# power.net
KiCad netlist of a schematic drawn in Altium Designer
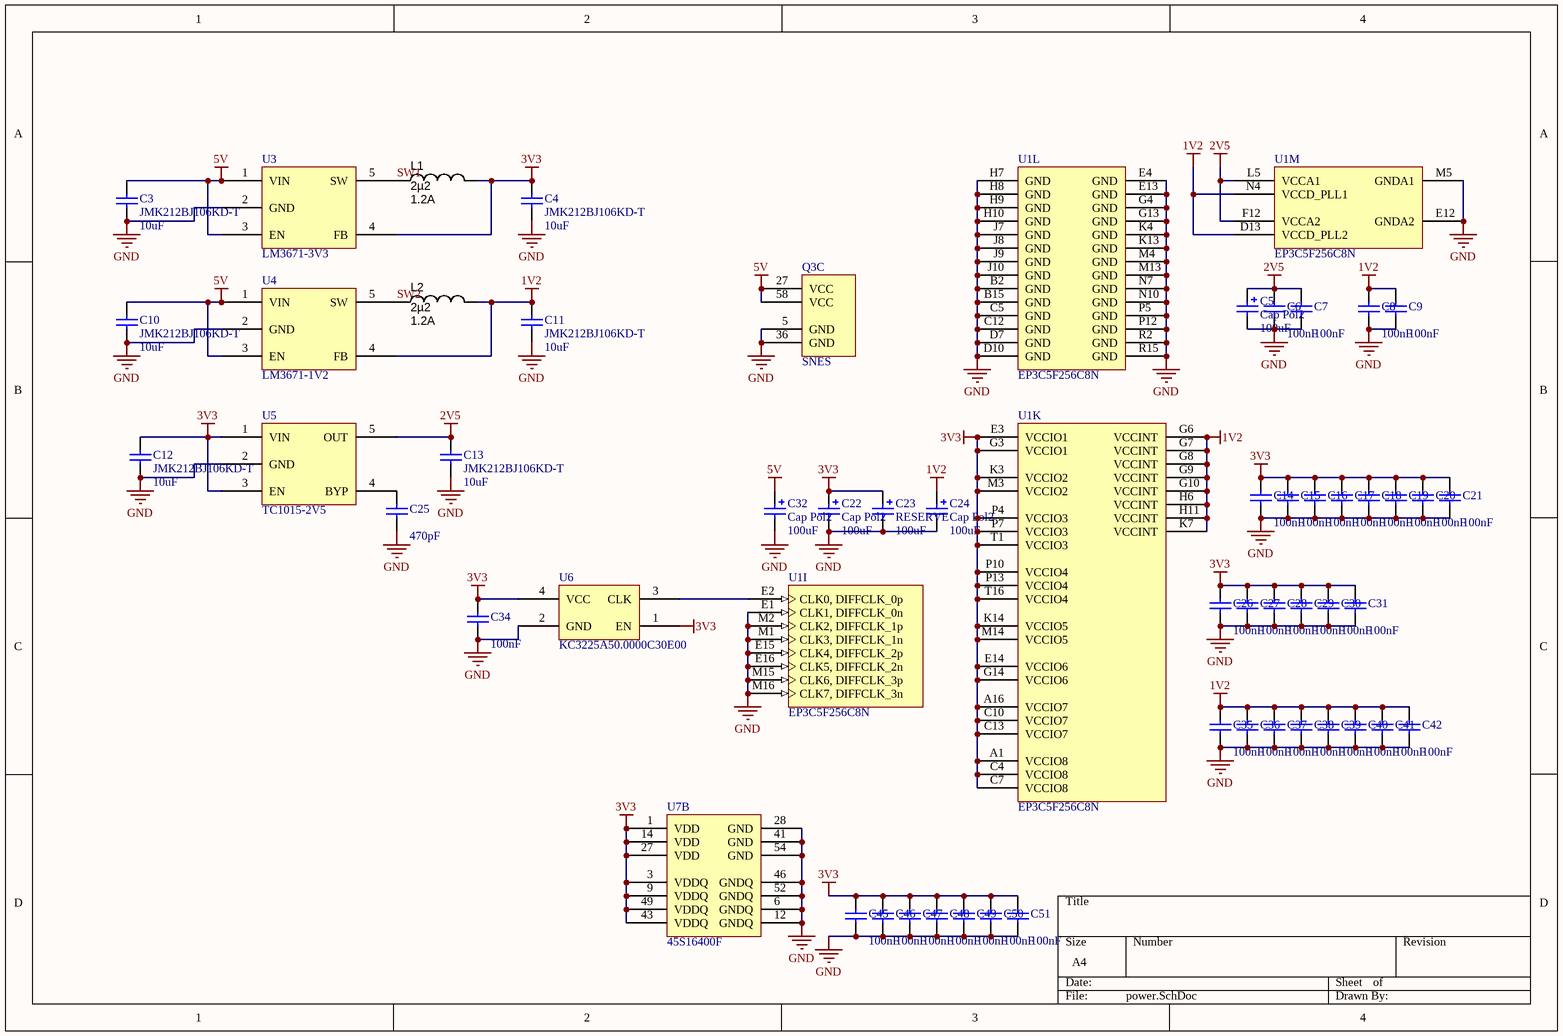
[diagram p0: power.SchDoc]

(export (version "E")
  (design (tool "Eeschema 10.0.6"))
  (components
    (comp (ref "C3")
      (value "JMK212BJ106KD-T")
      (footprint "CAPC2012X135N")
      (description "Capacitor")
      (fields (field (name "ALTIUM_VALUE") "10uF") (field (name "PUBLISHER") "Altium Limited"))
      (libsource (lib "Miscellaneous Devices") (part "Cap"))
    )
    (comp (ref "C4")
      (value "JMK212BJ106KD-T")
      (footprint "CAPC2012X135N")
      (description "Capacitor")
      (fields (field (name "ALTIUM_VALUE") "10uF") (field (name "PUBLISHER") "Altium Limited"))
      (libsource (lib "Miscellaneous Devices") (part "Cap"))
    )
    (comp (ref "C5")
      (value "Cap Pol2")
      (footprint "CAPC3225X220N")
      (description "Polarized Capacitor (Axial)")
      (fields (field (name "ALTIUM_VALUE") "100uF") (field (name "PUBLISHER") "Altium Limited"))
      (libsource (lib "Miscellaneous Devices") (part "Cap Pol2"))
    )
    (comp (ref "C6")
      (value "100nF")
      (footprint "CAPC1005X06L")
      (description "Capacitor")
      (fields (field (name "PUBLISHER") "Altium Limited"))
      (libsource (lib "Miscellaneous Devices") (part "Cap"))
    )
    (comp (ref "C7")
      (value "100nF")
      (footprint "CAPC1005X06L")
      (description "Capacitor")
      (fields (field (name "PUBLISHER") "Altium Limited"))
      (libsource (lib "Miscellaneous Devices") (part "Cap"))
    )
    (comp (ref "C8")
      (value "100nF")
      (footprint "CAPC1005X06L")
      (description "Capacitor")
      (fields (field (name "PUBLISHER") "Altium Limited"))
      (libsource (lib "Miscellaneous Devices") (part "Cap"))
    )
    (comp (ref "C9")
      (value "100nF")
      (footprint "CAPC1005X06L")
      (description "Capacitor")
      (fields (field (name "PUBLISHER") "Altium Limited"))
      (libsource (lib "Miscellaneous Devices") (part "Cap"))
    )
    (comp (ref "C10")
      (value "JMK212BJ106KD-T")
      (footprint "CAPC2012X135N")
      (description "Capacitor")
      (fields (field (name "ALTIUM_VALUE") "10uF") (field (name "PUBLISHER") "Altium Limited"))
      (libsource (lib "Miscellaneous Devices") (part "Cap"))
    )
    (comp (ref "C11")
      (value "JMK212BJ106KD-T")
      (footprint "CAPC2012X135N")
      (description "Capacitor")
      (fields (field (name "ALTIUM_VALUE") "10uF") (field (name "PUBLISHER") "Altium Limited"))
      (libsource (lib "Miscellaneous Devices") (part "Cap"))
    )
    (comp (ref "C12")
      (value "JMK212BJ106KD-T")
      (footprint "CAPC2012X135N")
      (description "Capacitor")
      (fields (field (name "ALTIUM_VALUE") "10uF") (field (name "PUBLISHER") "Altium Limited"))
      (libsource (lib "Miscellaneous Devices") (part "Cap"))
    )
    (comp (ref "C13")
      (value "JMK212BJ106KD-T")
      (footprint "CAPC2012X135N")
      (description "Capacitor")
      (fields (field (name "ALTIUM_VALUE") "10uF") (field (name "PUBLISHER") "Altium Limited"))
      (libsource (lib "Miscellaneous Devices") (part "Cap"))
    )
    (comp (ref "C14")
      (value "100nF")
      (footprint "CAPC1005X06L")
      (description "Capacitor")
      (fields (field (name "PUBLISHER") "Altium Limited"))
      (libsource (lib "Miscellaneous Devices") (part "Cap"))
    )
    (comp (ref "C15")
      (value "100nF")
      (footprint "CAPC1005X06L")
      (description "Capacitor")
      (fields (field (name "PUBLISHER") "Altium Limited"))
      (libsource (lib "Miscellaneous Devices") (part "Cap"))
    )
    (comp (ref "C16")
      (value "100nF")
      (footprint "CAPC1005X06L")
      (description "Capacitor")
      (fields (field (name "PUBLISHER") "Altium Limited"))
      (libsource (lib "Miscellaneous Devices") (part "Cap"))
    )
    (comp (ref "C17")
      (value "100nF")
      (footprint "CAPC1005X06L")
      (description "Capacitor")
      (fields (field (name "PUBLISHER") "Altium Limited"))
      (libsource (lib "Miscellaneous Devices") (part "Cap"))
    )
    (comp (ref "C18")
      (value "100nF")
      (footprint "CAPC1005X06L")
      (description "Capacitor")
      (fields (field (name "PUBLISHER") "Altium Limited"))
      (libsource (lib "Miscellaneous Devices") (part "Cap"))
    )
    (comp (ref "C19")
      (value "100nF")
      (footprint "CAPC1005X06L")
      (description "Capacitor")
      (fields (field (name "PUBLISHER") "Altium Limited"))
      (libsource (lib "Miscellaneous Devices") (part "Cap"))
    )
    (comp (ref "C20")
      (value "100nF")
      (footprint "CAPC1005X06L")
      (description "Capacitor")
      (fields (field (name "PUBLISHER") "Altium Limited"))
      (libsource (lib "Miscellaneous Devices") (part "Cap"))
    )
    (comp (ref "C21")
      (value "100nF")
      (footprint "CAPC1005X06L")
      (description "Capacitor")
      (fields (field (name "PUBLISHER") "Altium Limited"))
      (libsource (lib "Miscellaneous Devices") (part "Cap"))
    )
    (comp (ref "C22")
      (value "Cap Pol2")
      (footprint "CAPC3225X220N")
      (description "Polarized Capacitor (Axial)")
      (fields (field (name "ALTIUM_VALUE") "100uF") (field (name "PUBLISHER") "Altium Limited"))
      (libsource (lib "Miscellaneous Devices") (part "Cap Pol2"))
    )
    (comp (ref "C23")
      (value "RESERVE")
      (footprint "CAPC3225X220N")
      (description "Polarized Capacitor (Axial)")
      (fields (field (name "ALTIUM_VALUE") "100uF") (field (name "PUBLISHER") "Altium Limited"))
      (libsource (lib "Miscellaneous Devices") (part "Cap Pol2"))
    )
    (comp (ref "C24")
      (value "Cap Pol2")
      (footprint "CAPC3225X220N")
      (description "Polarized Capacitor (Axial)")
      (fields (field (name "ALTIUM_VALUE") "100uF") (field (name "PUBLISHER") "Altium Limited"))
      (libsource (lib "Miscellaneous Devices") (part "Cap Pol2"))
    )
    (comp (ref "C25")
      (value "470pF")
      (footprint "CAPC2012X135N")
      (description "Capacitor")
      (fields (field (name "PUBLISHER") "Altium Limited"))
      (libsource (lib "Miscellaneous Devices") (part "Cap"))
    )
    (comp (ref "C26")
      (value "100nF")
      (footprint "CAPC1005X06L")
      (description "Capacitor")
      (fields (field (name "PUBLISHER") "Altium Limited"))
      (libsource (lib "Miscellaneous Devices") (part "Cap"))
    )
    (comp (ref "C27")
      (value "100nF")
      (footprint "CAPC1005X06L")
      (description "Capacitor")
      (fields (field (name "PUBLISHER") "Altium Limited"))
      (libsource (lib "Miscellaneous Devices") (part "Cap"))
    )
    (comp (ref "C28")
      (value "100nF")
      (footprint "CAPC1005X06L")
      (description "Capacitor")
      (fields (field (name "PUBLISHER") "Altium Limited"))
      (libsource (lib "Miscellaneous Devices") (part "Cap"))
    )
    (comp (ref "C29")
      (value "100nF")
      (footprint "CAPC1005X06L")
      (description "Capacitor")
      (fields (field (name "PUBLISHER") "Altium Limited"))
      (libsource (lib "Miscellaneous Devices") (part "Cap"))
    )
    (comp (ref "C30")
      (value "100nF")
      (footprint "CAPC1005X06L")
      (description "Capacitor")
      (fields (field (name "PUBLISHER") "Altium Limited"))
      (libsource (lib "Miscellaneous Devices") (part "Cap"))
    )
    (comp (ref "C31")
      (value "100nF")
      (footprint "CAPC1005X06L")
      (description "Capacitor")
      (fields (field (name "PUBLISHER") "Altium Limited"))
      (libsource (lib "Miscellaneous Devices") (part "Cap"))
    )
    (comp (ref "C32")
      (value "Cap Pol2")
      (footprint "CAPC3225X220N")
      (description "Polarized Capacitor (Axial)")
      (fields (field (name "ALTIUM_VALUE") "100uF") (field (name "PUBLISHER") "Altium Limited"))
      (libsource (lib "Miscellaneous Devices") (part "Cap Pol2"))
    )
    (comp (ref "C34")
      (value "100nF")
      (footprint "CAPC1005X06L")
      (description "Capacitor")
      (fields (field (name "PUBLISHER") "Altium Limited"))
      (libsource (lib "Miscellaneous Devices") (part "Cap"))
    )
    (comp (ref "C35")
      (value "100nF")
      (footprint "CAPC1005X06L")
      (description "Capacitor")
      (fields (field (name "PUBLISHER") "Altium Limited"))
      (libsource (lib "Miscellaneous Devices") (part "Cap"))
    )
    (comp (ref "C36")
      (value "100nF")
      (footprint "CAPC1005X06L")
      (description "Capacitor")
      (fields (field (name "PUBLISHER") "Altium Limited"))
      (libsource (lib "Miscellaneous Devices") (part "Cap"))
    )
    (comp (ref "C37")
      (value "100nF")
      (footprint "CAPC1005X06L")
      (description "Capacitor")
      (fields (field (name "PUBLISHER") "Altium Limited"))
      (libsource (lib "Miscellaneous Devices") (part "Cap"))
    )
    (comp (ref "C38")
      (value "100nF")
      (footprint "CAPC1005X06L")
      (description "Capacitor")
      (fields (field (name "PUBLISHER") "Altium Limited"))
      (libsource (lib "Miscellaneous Devices") (part "Cap"))
    )
    (comp (ref "C39")
      (value "100nF")
      (footprint "CAPC1005X06L")
      (description "Capacitor")
      (fields (field (name "PUBLISHER") "Altium Limited"))
      (libsource (lib "Miscellaneous Devices") (part "Cap"))
    )
    (comp (ref "C40")
      (value "100nF")
      (footprint "CAPC1005X06L")
      (description "Capacitor")
      (fields (field (name "PUBLISHER") "Altium Limited"))
      (libsource (lib "Miscellaneous Devices") (part "Cap"))
    )
    (comp (ref "C41")
      (value "100nF")
      (footprint "CAPC1005X06L")
      (description "Capacitor")
      (fields (field (name "PUBLISHER") "Altium Limited"))
      (libsource (lib "Miscellaneous Devices") (part "Cap"))
    )
    (comp (ref "C42")
      (value "100nF")
      (footprint "CAPC1005X06L")
      (description "Capacitor")
      (fields (field (name "PUBLISHER") "Altium Limited"))
      (libsource (lib "Miscellaneous Devices") (part "Cap"))
    )
    (comp (ref "C45")
      (value "100nF")
      (footprint "CAPC1005X06L")
      (description "Capacitor")
      (fields (field (name "PUBLISHER") "Altium Limited"))
      (libsource (lib "Miscellaneous Devices") (part "Cap"))
    )
    (comp (ref "C46")
      (value "100nF")
      (footprint "CAPC1005X06L")
      (description "Capacitor")
      (fields (field (name "PUBLISHER") "Altium Limited"))
      (libsource (lib "Miscellaneous Devices") (part "Cap"))
    )
    (comp (ref "C47")
      (value "100nF")
      (footprint "CAPC1005X06L")
      (description "Capacitor")
      (fields (field (name "PUBLISHER") "Altium Limited"))
      (libsource (lib "Miscellaneous Devices") (part "Cap"))
    )
    (comp (ref "C48")
      (value "100nF")
      (footprint "CAPC1005X06L")
      (description "Capacitor")
      (fields (field (name "PUBLISHER") "Altium Limited"))
      (libsource (lib "Miscellaneous Devices") (part "Cap"))
    )
    (comp (ref "C49")
      (value "100nF")
      (footprint "CAPC1005X06L")
      (description "Capacitor")
      (fields (field (name "PUBLISHER") "Altium Limited"))
      (libsource (lib "Miscellaneous Devices") (part "Cap"))
    )
    (comp (ref "C50")
      (value "100nF")
      (footprint "CAPC1005X06L")
      (description "Capacitor")
      (fields (field (name "PUBLISHER") "Altium Limited"))
      (libsource (lib "Miscellaneous Devices") (part "Cap"))
    )
    (comp (ref "C51")
      (value "100nF")
      (footprint "CAPC1005X06L")
      (description "Capacitor")
      (fields (field (name "PUBLISHER") "Altium Limited"))
      (libsource (lib "Miscellaneous Devices") (part "Cap"))
    )
    (comp (ref "L1")
      (value "1.2A")
      (footprint "INDM3225X240N")
      (description "Inductor 2.2uH 1.2A 1210 SMD chip")
      (fields (field (name "TOLERANCE") "±20%") (field (name "ALTIUM_VALUE") "2µ2"))
      (libsource (lib "PBL - Inductors") (part "INDC_2u2_1210_1200mA"))
    )
    (comp (ref "L2")
      (value "1.2A")
      (footprint "INDM3225X240N")
      (description "Inductor 2.2uH 1.2A 1210 SMD chip")
      (fields (field (name "TOLERANCE") "±20%") (field (name "ALTIUM_VALUE") "2µ2"))
      (libsource (lib "PBL - Inductors") (part "INDC_2u2_1210_1200mA"))
    )
    (comp (ref "Q3") (value "SNES") (footprint "SNES") (libsource (lib "parts") (part "SNES")))
    (comp (ref "U1")
      (value "EP3C5F256C8N")
      (footprint "FBGA256-2")
      (fields (field (name "PUBLISHER") "Altium Limited"))
      (libsource (lib "Altera Cyclone III") (part "EP3C5F256C8N"))
    )
    (comp (ref "U3") (value "LM3671-3V3") (footprint "SOT23-5") (libsource (lib "parts") (part "LM3671")))
    (comp (ref "U4") (value "LM3671-1V2") (footprint "SOT23-5") (libsource (lib "parts") (part "LM3671")))
    (comp (ref "U5") (value "TC1015-2V5") (footprint "SOT23-5") (libsource (lib "parts") (part "TC1015")))
    (comp (ref "U6")
      (value "KC3225A50.0000C30E00")
      (footprint "KC3225A")
      (libsource (lib "parts") (part "osc"))
    )
    (comp (ref "U7")
      (value "45S16400F")
      (footprint "TSOP2-54_N")
      (libsource (lib "parts") (part "45S16400F"))
    )
  )
  (nets
    (net (code "1") (name "/SW1") (class "Default")
      (node (ref "L1") (pin "1") (pinfunction "1_1") (pintype "passive"))
      (node (ref "U3") (pin "5") (pinfunction "SW_5") (pintype "passive"))
    )
    (net (code "2") (name "/SW2") (class "Default")
      (node (ref "L2") (pin "1") (pinfunction "1_1") (pintype "passive"))
      (node (ref "U4") (pin "5") (pinfunction "SW_5") (pintype "passive"))
    )
    (net (code "3") (name "1V2") (class "Default")
      (node (ref "C11") (pin "2") (pinfunction "2_2") (pintype "passive"))
      (node (ref "C24") (pin "1") (pinfunction "1_1") (pintype "passive"))
      (node (ref "C35") (pin "2") (pinfunction "2_2") (pintype "passive"))
      (node (ref "C36") (pin "2") (pinfunction "2_2") (pintype "passive"))
      (node (ref "C37") (pin "2") (pinfunction "2_2") (pintype "passive"))
      (node (ref "C38") (pin "2") (pinfunction "2_2") (pintype "passive"))
      (node (ref "C39") (pin "2") (pinfunction "2_2") (pintype "passive"))
      (node (ref "C40") (pin "2") (pinfunction "2_2") (pintype "passive"))
      (node (ref "C41") (pin "2") (pinfunction "2_2") (pintype "passive"))
      (node (ref "C42") (pin "2") (pinfunction "2_2") (pintype "passive"))
      (node (ref "C8") (pin "2") (pinfunction "2_2") (pintype "passive"))
      (node (ref "C9") (pin "2") (pinfunction "2_2") (pintype "passive"))
      (node (ref "L2") (pin "2") (pinfunction "2_2") (pintype "passive"))
      (node (ref "U1") (pin "D13") (pinfunction "VCCD_PLL2_D13") (pintype "power_in"))
      (node (ref "U1") (pin "G10") (pinfunction "VCCINT_G10") (pintype "power_in"))
      (node (ref "U1") (pin "G6") (pinfunction "VCCINT_G6") (pintype "power_in"))
      (node (ref "U1") (pin "G7") (pinfunction "VCCINT_G7") (pintype "power_in"))
      (node (ref "U1") (pin "G8") (pinfunction "VCCINT_G8") (pintype "power_in"))
      (node (ref "U1") (pin "G9") (pinfunction "VCCINT_G9") (pintype "power_in"))
      (node (ref "U1") (pin "H11") (pinfunction "VCCINT_H11") (pintype "power_in"))
      (node (ref "U1") (pin "H6") (pinfunction "VCCINT_H6") (pintype "power_in"))
      (node (ref "U1") (pin "K7") (pinfunction "VCCINT_K7") (pintype "power_in"))
      (node (ref "U1") (pin "N4") (pinfunction "VCCD_PLL1_N4") (pintype "power_in"))
      (node (ref "U4") (pin "4") (pinfunction "FB_4") (pintype "passive"))
    )
    (net (code "4") (name "2V5") (class "Default")
      (node (ref "C13") (pin "2") (pinfunction "2_2") (pintype "passive"))
      (node (ref "C5") (pin "1") (pinfunction "1_1") (pintype "passive"))
      (node (ref "C6") (pin "2") (pinfunction "2_2") (pintype "passive"))
      (node (ref "C7") (pin "2") (pinfunction "2_2") (pintype "passive"))
      (node (ref "U1") (pin "F12") (pinfunction "VCCA2_F12") (pintype "power_in"))
      (node (ref "U1") (pin "L5") (pinfunction "VCCA1_L5") (pintype "power_in"))
      (node (ref "U5") (pin "5") (pinfunction "OUT_5") (pintype "passive"))
    )
    (net (code "5") (name "3V3") (class "Default")
      (node (ref "C12") (pin "2") (pinfunction "2_2") (pintype "passive"))
      (node (ref "C14") (pin "2") (pinfunction "2_2") (pintype "passive"))
      (node (ref "C15") (pin "2") (pinfunction "2_2") (pintype "passive"))
      (node (ref "C16") (pin "2") (pinfunction "2_2") (pintype "passive"))
      (node (ref "C17") (pin "2") (pinfunction "2_2") (pintype "passive"))
      (node (ref "C18") (pin "2") (pinfunction "2_2") (pintype "passive"))
      (node (ref "C19") (pin "2") (pinfunction "2_2") (pintype "passive"))
      (node (ref "C20") (pin "2") (pinfunction "2_2") (pintype "passive"))
      (node (ref "C21") (pin "2") (pinfunction "2_2") (pintype "passive"))
      (node (ref "C22") (pin "1") (pinfunction "1_1") (pintype "passive"))
      (node (ref "C23") (pin "1") (pinfunction "1_1") (pintype "passive"))
      (node (ref "C26") (pin "2") (pinfunction "2_2") (pintype "passive"))
      (node (ref "C27") (pin "2") (pinfunction "2_2") (pintype "passive"))
      (node (ref "C28") (pin "2") (pinfunction "2_2") (pintype "passive"))
      (node (ref "C29") (pin "2") (pinfunction "2_2") (pintype "passive"))
      (node (ref "C30") (pin "2") (pinfunction "2_2") (pintype "passive"))
      (node (ref "C31") (pin "2") (pinfunction "2_2") (pintype "passive"))
      (node (ref "C34") (pin "2") (pinfunction "2_2") (pintype "passive"))
      (node (ref "C4") (pin "2") (pinfunction "2_2") (pintype "passive"))
      (node (ref "C45") (pin "2") (pinfunction "2_2") (pintype "passive"))
      (node (ref "C46") (pin "2") (pinfunction "2_2") (pintype "passive"))
      (node (ref "C47") (pin "2") (pinfunction "2_2") (pintype "passive"))
      (node (ref "C48") (pin "2") (pinfunction "2_2") (pintype "passive"))
      (node (ref "C49") (pin "2") (pinfunction "2_2") (pintype "passive"))
      (node (ref "C50") (pin "2") (pinfunction "2_2") (pintype "passive"))
      (node (ref "C51") (pin "2") (pinfunction "2_2") (pintype "passive"))
      (node (ref "L1") (pin "2") (pinfunction "2_2") (pintype "passive"))
      (node (ref "U1") (pin "A1") (pinfunction "VCCIO8_A1") (pintype "power_in"))
      (node (ref "U1") (pin "A16") (pinfunction "VCCIO7_A16") (pintype "power_in"))
      (node (ref "U1") (pin "C10") (pinfunction "VCCIO7_C10") (pintype "power_in"))
      (node (ref "U1") (pin "C13") (pinfunction "VCCIO7_C13") (pintype "power_in"))
      (node (ref "U1") (pin "C4") (pinfunction "VCCIO8_C4") (pintype "power_in"))
      (node (ref "U1") (pin "C7") (pinfunction "VCCIO8_C7") (pintype "power_in"))
      (node (ref "U1") (pin "E14") (pinfunction "VCCIO6_E14") (pintype "power_in"))
      (node (ref "U1") (pin "E3") (pinfunction "VCCIO1_E3") (pintype "power_in"))
      (node (ref "U1") (pin "G14") (pinfunction "VCCIO6_G14") (pintype "power_in"))
      (node (ref "U1") (pin "G3") (pinfunction "VCCIO1_G3") (pintype "power_in"))
      (node (ref "U1") (pin "K14") (pinfunction "VCCIO5_K14") (pintype "power_in"))
      (node (ref "U1") (pin "K3") (pinfunction "VCCIO2_K3") (pintype "power_in"))
      (node (ref "U1") (pin "M14") (pinfunction "VCCIO5_M14") (pintype "power_in"))
      (node (ref "U1") (pin "M3") (pinfunction "VCCIO2_M3") (pintype "power_in"))
      (node (ref "U1") (pin "P10") (pinfunction "VCCIO4_P10") (pintype "power_in"))
      (node (ref "U1") (pin "P13") (pinfunction "VCCIO4_P13") (pintype "power_in"))
      (node (ref "U1") (pin "P4") (pinfunction "VCCIO3_P4") (pintype "power_in"))
      (node (ref "U1") (pin "P7") (pinfunction "VCCIO3_P7") (pintype "power_in"))
      (node (ref "U1") (pin "T1") (pinfunction "VCCIO3_T1") (pintype "power_in"))
      (node (ref "U1") (pin "T16") (pinfunction "VCCIO4_T16") (pintype "power_in"))
      (node (ref "U3") (pin "4") (pinfunction "FB_4") (pintype "passive"))
      (node (ref "U5") (pin "1") (pinfunction "VIN_1") (pintype "passive"))
      (node (ref "U5") (pin "3") (pinfunction "EN_3") (pintype "passive"))
      (node (ref "U6") (pin "1") (pinfunction "EN_1") (pintype "passive"))
      (node (ref "U6") (pin "4") (pinfunction "VCC_4") (pintype "passive"))
      (node (ref "U7") (pin "1") (pinfunction "VDD_1") (pintype "passive"))
      (node (ref "U7") (pin "14") (pinfunction "VDD_14") (pintype "passive"))
      (node (ref "U7") (pin "27") (pinfunction "VDD_27") (pintype "passive"))
      (node (ref "U7") (pin "3") (pinfunction "VDDQ_3") (pintype "passive"))
      (node (ref "U7") (pin "43") (pinfunction "VDDQ_43") (pintype "passive"))
      (node (ref "U7") (pin "49") (pinfunction "VDDQ_49") (pintype "passive"))
      (node (ref "U7") (pin "9") (pinfunction "VDDQ_9") (pintype "passive"))
    )
    (net (code "6") (name "5V") (class "Default")
      (node (ref "C10") (pin "2") (pinfunction "2_2") (pintype "passive"))
      (node (ref "C3") (pin "2") (pinfunction "2_2") (pintype "passive"))
      (node (ref "C32") (pin "1") (pinfunction "1_1") (pintype "passive"))
      (node (ref "Q3") (pin "27") (pinfunction "VCC_27") (pintype "passive"))
      (node (ref "Q3") (pin "58") (pinfunction "VCC_58") (pintype "passive"))
      (node (ref "U3") (pin "1") (pinfunction "VIN_1") (pintype "passive"))
      (node (ref "U3") (pin "3") (pinfunction "EN_3") (pintype "passive"))
      (node (ref "U4") (pin "1") (pinfunction "VIN_1") (pintype "passive"))
      (node (ref "U4") (pin "3") (pinfunction "EN_3") (pintype "passive"))
    )
    (net (code "7") (name "GND") (class "Default")
      (node (ref "C10") (pin "1") (pinfunction "1_1") (pintype "passive"))
      (node (ref "C11") (pin "1") (pinfunction "1_1") (pintype "passive"))
      (node (ref "C12") (pin "1") (pinfunction "1_1") (pintype "passive"))
      (node (ref "C13") (pin "1") (pinfunction "1_1") (pintype "passive"))
      (node (ref "C14") (pin "1") (pinfunction "1_1") (pintype "passive"))
      (node (ref "C15") (pin "1") (pinfunction "1_1") (pintype "passive"))
      (node (ref "C16") (pin "1") (pinfunction "1_1") (pintype "passive"))
      (node (ref "C17") (pin "1") (pinfunction "1_1") (pintype "passive"))
      (node (ref "C18") (pin "1") (pinfunction "1_1") (pintype "passive"))
      (node (ref "C19") (pin "1") (pinfunction "1_1") (pintype "passive"))
      (node (ref "C20") (pin "1") (pinfunction "1_1") (pintype "passive"))
      (node (ref "C21") (pin "1") (pinfunction "1_1") (pintype "passive"))
      (node (ref "C22") (pin "2") (pinfunction "2_2") (pintype "passive"))
      (node (ref "C23") (pin "2") (pinfunction "2_2") (pintype "passive"))
      (node (ref "C24") (pin "2") (pinfunction "2_2") (pintype "passive"))
      (node (ref "C25") (pin "1") (pinfunction "1_1") (pintype "passive"))
      (node (ref "C26") (pin "1") (pinfunction "1_1") (pintype "passive"))
      (node (ref "C27") (pin "1") (pinfunction "1_1") (pintype "passive"))
      (node (ref "C28") (pin "1") (pinfunction "1_1") (pintype "passive"))
      (node (ref "C29") (pin "1") (pinfunction "1_1") (pintype "passive"))
      (node (ref "C3") (pin "1") (pinfunction "1_1") (pintype "passive"))
      (node (ref "C30") (pin "1") (pinfunction "1_1") (pintype "passive"))
      (node (ref "C31") (pin "1") (pinfunction "1_1") (pintype "passive"))
      (node (ref "C32") (pin "2") (pinfunction "2_2") (pintype "passive"))
      (node (ref "C34") (pin "1") (pinfunction "1_1") (pintype "passive"))
      (node (ref "C35") (pin "1") (pinfunction "1_1") (pintype "passive"))
      (node (ref "C36") (pin "1") (pinfunction "1_1") (pintype "passive"))
      (node (ref "C37") (pin "1") (pinfunction "1_1") (pintype "passive"))
      (node (ref "C38") (pin "1") (pinfunction "1_1") (pintype "passive"))
      (node (ref "C39") (pin "1") (pinfunction "1_1") (pintype "passive"))
      (node (ref "C4") (pin "1") (pinfunction "1_1") (pintype "passive"))
      (node (ref "C40") (pin "1") (pinfunction "1_1") (pintype "passive"))
      (node (ref "C41") (pin "1") (pinfunction "1_1") (pintype "passive"))
      (node (ref "C42") (pin "1") (pinfunction "1_1") (pintype "passive"))
      (node (ref "C45") (pin "1") (pinfunction "1_1") (pintype "passive"))
      (node (ref "C46") (pin "1") (pinfunction "1_1") (pintype "passive"))
      (node (ref "C47") (pin "1") (pinfunction "1_1") (pintype "passive"))
      (node (ref "C48") (pin "1") (pinfunction "1_1") (pintype "passive"))
      (node (ref "C49") (pin "1") (pinfunction "1_1") (pintype "passive"))
      (node (ref "C5") (pin "2") (pinfunction "2_2") (pintype "passive"))
      (node (ref "C50") (pin "1") (pinfunction "1_1") (pintype "passive"))
      (node (ref "C51") (pin "1") (pinfunction "1_1") (pintype "passive"))
      (node (ref "C6") (pin "1") (pinfunction "1_1") (pintype "passive"))
      (node (ref "C7") (pin "1") (pinfunction "1_1") (pintype "passive"))
      (node (ref "C8") (pin "1") (pinfunction "1_1") (pintype "passive"))
      (node (ref "C9") (pin "1") (pinfunction "1_1") (pintype "passive"))
      (node (ref "Q3") (pin "36") (pinfunction "GND_36") (pintype "passive"))
      (node (ref "Q3") (pin "5") (pinfunction "GND_5") (pintype "passive"))
      (node (ref "U1") (pin "B15") (pinfunction "GND_B15") (pintype "power_in"))
      (node (ref "U1") (pin "B2") (pinfunction "GND_B2") (pintype "power_in"))
      (node (ref "U1") (pin "C12") (pinfunction "GND_C12") (pintype "power_in"))
      (node (ref "U1") (pin "C5") (pinfunction "GND_C5") (pintype "power_in"))
      (node (ref "U1") (pin "D10") (pinfunction "GND_D10") (pintype "power_in"))
      (node (ref "U1") (pin "D7") (pinfunction "GND_D7") (pintype "power_in"))
      (node (ref "U1") (pin "E1") (pinfunction "CLK1,_DIFFCLK_0n_E1") (pintype "input"))
      (node (ref "U1") (pin "E12") (pinfunction "GNDA2_E12") (pintype "power_in"))
      (node (ref "U1") (pin "E13") (pinfunction "GND_E13") (pintype "power_in"))
      (node (ref "U1") (pin "E15") (pinfunction "CLK4,_DIFFCLK_2p_E15") (pintype "input"))
      (node (ref "U1") (pin "E16") (pinfunction "CLK5,_DIFFCLK_2n_E16") (pintype "input"))
      (node (ref "U1") (pin "E4") (pinfunction "GND_E4") (pintype "power_in"))
      (node (ref "U1") (pin "G13") (pinfunction "GND_G13") (pintype "power_in"))
      (node (ref "U1") (pin "G4") (pinfunction "GND_G4") (pintype "power_in"))
      (node (ref "U1") (pin "H10") (pinfunction "GND_H10") (pintype "power_in"))
      (node (ref "U1") (pin "H7") (pinfunction "GND_H7") (pintype "power_in"))
      (node (ref "U1") (pin "H8") (pinfunction "GND_H8") (pintype "power_in"))
      (node (ref "U1") (pin "H9") (pinfunction "GND_H9") (pintype "power_in"))
      (node (ref "U1") (pin "J10") (pinfunction "GND_J10") (pintype "power_in"))
      (node (ref "U1") (pin "J7") (pinfunction "GND_J7") (pintype "power_in"))
      (node (ref "U1") (pin "J8") (pinfunction "GND_J8") (pintype "power_in"))
      (node (ref "U1") (pin "J9") (pinfunction "GND_J9") (pintype "power_in"))
      (node (ref "U1") (pin "K13") (pinfunction "GND_K13") (pintype "power_in"))
      (node (ref "U1") (pin "K4") (pinfunction "GND_K4") (pintype "power_in"))
      (node (ref "U1") (pin "M1") (pinfunction "CLK3,_DIFFCLK_1n_M1") (pintype "input"))
      (node (ref "U1") (pin "M13") (pinfunction "GND_M13") (pintype "power_in"))
      (node (ref "U1") (pin "M15") (pinfunction "CLK6,_DIFFCLK_3p_M15") (pintype "input"))
      (node (ref "U1") (pin "M16") (pinfunction "CLK7,_DIFFCLK_3n_M16") (pintype "input"))
      (node (ref "U1") (pin "M2") (pinfunction "CLK2,_DIFFCLK_1p_M2") (pintype "input"))
      (node (ref "U1") (pin "M4") (pinfunction "GND_M4") (pintype "power_in"))
      (node (ref "U1") (pin "M5") (pinfunction "GNDA1_M5") (pintype "power_in"))
      (node (ref "U1") (pin "N10") (pinfunction "GND_N10") (pintype "power_in"))
      (node (ref "U1") (pin "N7") (pinfunction "GND_N7") (pintype "power_in"))
      (node (ref "U1") (pin "P12") (pinfunction "GND_P12") (pintype "power_in"))
      (node (ref "U1") (pin "P5") (pinfunction "GND_P5") (pintype "power_in"))
      (node (ref "U1") (pin "R15") (pinfunction "GND_R15") (pintype "power_in"))
      (node (ref "U1") (pin "R2") (pinfunction "GND_R2") (pintype "power_in"))
      (node (ref "U3") (pin "2") (pinfunction "GND_2") (pintype "passive"))
      (node (ref "U4") (pin "2") (pinfunction "GND_2") (pintype "passive"))
      (node (ref "U5") (pin "2") (pinfunction "GND_2") (pintype "passive"))
      (node (ref "U6") (pin "2") (pinfunction "GND_2") (pintype "passive"))
      (node (ref "U7") (pin "12") (pinfunction "GNDQ_12") (pintype "passive"))
      (node (ref "U7") (pin "28") (pinfunction "GND_28") (pintype "passive"))
      (node (ref "U7") (pin "41") (pinfunction "GND_41") (pintype "passive"))
      (node (ref "U7") (pin "46") (pinfunction "GNDQ_46") (pintype "passive"))
      (node (ref "U7") (pin "52") (pinfunction "GNDQ_52") (pintype "passive"))
      (node (ref "U7") (pin "54") (pinfunction "GND_54") (pintype "passive"))
      (node (ref "U7") (pin "6") (pinfunction "GNDQ_6") (pintype "passive"))
    )
    (net (code "8") (name "Net-(U1I-CLK0,_DIFFCLK_0p)") (class "Default")
      (node (ref "U1") (pin "E2") (pinfunction "CLK0,_DIFFCLK_0p_E2") (pintype "input"))
      (node (ref "U6") (pin "3") (pinfunction "CLK_3") (pintype "passive"))
    )
    (net (code "9") (name "Net-(U5-BYP)") (class "Default")
      (node (ref "C25") (pin "2") (pinfunction "2_2") (pintype "passive"))
      (node (ref "U5") (pin "4") (pinfunction "BYP_4") (pintype "passive"))
    )
  )
)
